# STM32_CONNECTORS.net
KiCad netlist of a schematic drawn in Altium Designer
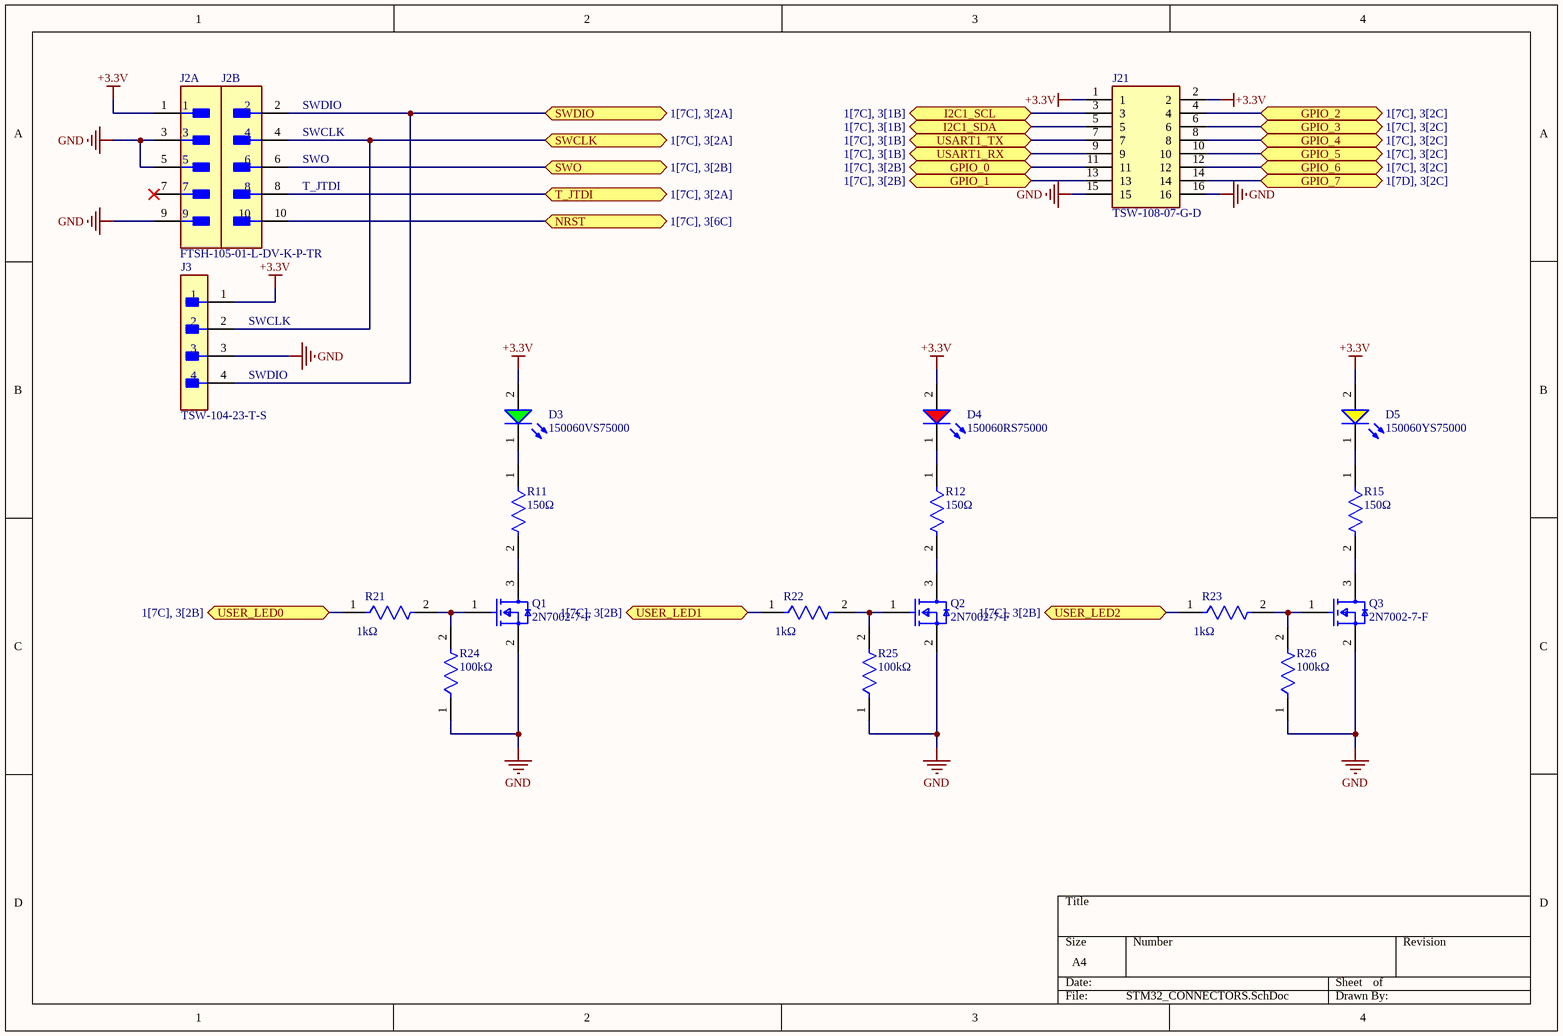
[diagram p0: STM32_CONNECTORS.SchDoc]

(export (version "E")
  (design (tool "Eeschema 10.0.6"))
  (components
    (comp (ref "D3")
      (value "150060VS75000")
      (footprint "WL-SMCW_0603_150060xx75000")
      (libsource (lib "Altium Content Vault") (part "LED_Green_2A-1K"))
    )
    (comp (ref "D4")
      (value "150060RS75000")
      (footprint "WL-SMCW_0603_150060xx75000")
      (libsource (lib "Altium Content Vault") (part "LED_Red_2A-1K"))
    )
    (comp (ref "D5")
      (value "150060YS75000")
      (footprint "WL-SMCW_0603_150060xx75000")
      (libsource (lib "Altium Content Vault") (part "LED_Yellow_2A-1K"))
    )
    (comp (ref "J2")
      (value "FTSH-105-01-L-DV-K-P-TR")
      (footprint "FP-FTSH-105-01-L-DV-K-P-T-MFG")
      (description "CONN HEADER SMD 10POS 1.27MM")
      (libsource (lib "") (part "544f42128f4185dcb88ce1ce9bf1982_1"))
    )
    (comp (ref "J3")
      (value "TSW-104-23-T-S")
      (footprint "FP-TSW-104-23-T-S-MFG")
      (description "CONN HEADER VERT 4POS 2.54MM")
      (libsource (lib "Altium Content Vault") (part "f33e0d423099bbb9e64512431cdbdf7"))
    )
    (comp (ref "J21")
      (value "TSW-108-07-G-D")
      (footprint "SamacSys:HDRV16W64P254_2X8_2032X508X838P")
      (description "Connector")
      (fields (field (name "MOUSER PART NUMBER") "200-TSW10807GD"))
      (libsource (lib "*") (part "TSW-108-07-G-D"))
    )
    (comp (ref "Q1")
      (value "2N7002-7-F")
      (footprint "FP-SOT23-IPC_A")
      (description "MOSFET N-CH 60V 115MA SOT23-3")
      (fields (field (name "VOLTAGE") "60V"))
      (libsource (lib "Altium Content Vault") (part "3b9c635fedb024a5347a57b145af9cc"))
    )
    (comp (ref "Q2")
      (value "2N7002-7-F")
      (footprint "FP-SOT23-IPC_A")
      (description "MOSFET N-CH 60V 115MA SOT23-3")
      (fields (field (name "VOLTAGE") "60V"))
      (libsource (lib "Altium Content Vault") (part "3b9c635fedb024a5347a57b145af9cc"))
    )
    (comp (ref "Q3")
      (value "2N7002-7-F")
      (footprint "FP-SOT23-IPC_A")
      (description "MOSFET N-CH 60V 115MA SOT23-3")
      (fields (field (name "VOLTAGE") "60V"))
      (libsource (lib "Altium Content Vault") (part "3b9c635fedb024a5347a57b145af9cc"))
    )
    (comp (ref "R11")
      (value "CRCW0603150RFKEA")
      (footprint "FP-CRCW0603-e3-IPC_B")
      (description "RES Thick Film, 150Ω, 1%, 0.1W, 100ppm/°C, 0603")
      (fields (field (name "TOLERANCE") "1%") (field (name "RESISTANCE") "150Ω"))
      (libsource (lib "Altium Content Vault") (part "1029c3af85768c4190bb7ad29bc67b5"))
    )
    (comp (ref "R12")
      (value "CRCW0603150RFKEA")
      (footprint "FP-CRCW0603-e3-IPC_B")
      (description "RES Thick Film, 150Ω, 1%, 0.1W, 100ppm/°C, 0603")
      (fields (field (name "TOLERANCE") "1%") (field (name "RESISTANCE") "150Ω"))
      (libsource (lib "Altium Content Vault") (part "1029c3af85768c4190bb7ad29bc67b5"))
    )
    (comp (ref "R15")
      (value "CRCW0603150RFKEA")
      (footprint "FP-CRCW0603-e3-IPC_B")
      (description "RES Thick Film, 150Ω, 1%, 0.1W, 100ppm/°C, 0603")
      (fields (field (name "TOLERANCE") "1%") (field (name "RESISTANCE") "150Ω"))
      (libsource (lib "Altium Content Vault") (part "1029c3af85768c4190bb7ad29bc67b5"))
    )
    (comp (ref "R21")
      (value "AC0603FR-071KL")
      (footprint "FP-AC0603-IPC_B")
      (description "RES 1kΩ 1.00% 0.1W 0603")
      (fields (field (name "TOLERANCE") "1%") (field (name "RESISTANCE") "1kΩ"))
      (libsource (lib "Altium Content Vault") (part "1029c3af85768c4190bb7ad29bc67b5"))
    )
    (comp (ref "R22")
      (value "AC0603FR-071KL")
      (footprint "FP-AC0603-IPC_B")
      (description "RES 1kΩ 1.00% 0.1W 0603")
      (fields (field (name "TOLERANCE") "1%") (field (name "RESISTANCE") "1kΩ"))
      (libsource (lib "Altium Content Vault") (part "1029c3af85768c4190bb7ad29bc67b5"))
    )
    (comp (ref "R23")
      (value "AC0603FR-071KL")
      (footprint "FP-AC0603-IPC_B")
      (description "RES 1kΩ 1.00% 0.1W 0603")
      (fields (field (name "TOLERANCE") "1%") (field (name "RESISTANCE") "1kΩ"))
      (libsource (lib "Altium Content Vault") (part "1029c3af85768c4190bb7ad29bc67b5"))
    )
    (comp (ref "R24")
      (value "CRCW0603100KFKEC")
      (footprint "FP-CRCW0603-e3-IPC_B")
      (description "RES Thick Film, 100kΩ, 1%, 0.1W, 100ppm/°C, 0603")
      (fields (field (name "RESISTANCE") "100kΩ") (field (name "TOLERANCE") "1%"))
      (libsource (lib "Altium Content Vault") (part "1029c3af85768c4190bb7ad29bc67b5"))
    )
    (comp (ref "R25")
      (value "CRCW0603100KFKEC")
      (footprint "FP-CRCW0603-e3-IPC_B")
      (description "RES Thick Film, 100kΩ, 1%, 0.1W, 100ppm/°C, 0603")
      (fields (field (name "RESISTANCE") "100kΩ") (field (name "TOLERANCE") "1%"))
      (libsource (lib "Altium Content Vault") (part "1029c3af85768c4190bb7ad29bc67b5"))
    )
    (comp (ref "R26")
      (value "CRCW0603100KFKEC")
      (footprint "FP-CRCW0603-e3-IPC_B")
      (description "RES Thick Film, 100kΩ, 1%, 0.1W, 100ppm/°C, 0603")
      (fields (field (name "RESISTANCE") "100kΩ") (field (name "TOLERANCE") "1%"))
      (libsource (lib "Altium Content Vault") (part "1029c3af85768c4190bb7ad29bc67b5"))
    )
  )
  (nets
    (net (code "1") (name "+3.3V") (class "Default")
      (node (ref "D3") (pin "2") (pinfunction "A_2") (pintype "passive"))
      (node (ref "D4") (pin "2") (pinfunction "A_2") (pintype "passive"))
      (node (ref "D5") (pin "2") (pinfunction "A_2") (pintype "passive"))
      (node (ref "J2") (pin "1") (pinfunction "1_1") (pintype "passive"))
      (node (ref "J21") (pin "1") (pinfunction "1_1") (pintype "passive"))
      (node (ref "J21") (pin "2") (pinfunction "2_2") (pintype "passive"))
      (node (ref "J3") (pin "1") (pinfunction "1_1") (pintype "passive"))
    )
    (net (code "2") (name "/GPIO_0") (class "Default")
      (node (ref "J21") (pin "11") (pinfunction "11_11") (pintype "passive"))
    )
    (net (code "3") (name "/GPIO_1") (class "Default")
      (node (ref "J21") (pin "13") (pinfunction "13_13") (pintype "passive"))
    )
    (net (code "4") (name "/GPIO_2") (class "Default")
      (node (ref "J21") (pin "4") (pinfunction "4_4") (pintype "passive"))
    )
    (net (code "5") (name "/GPIO_3") (class "Default")
      (node (ref "J21") (pin "6") (pinfunction "6_6") (pintype "passive"))
    )
    (net (code "6") (name "/GPIO_4") (class "Default")
      (node (ref "J21") (pin "8") (pinfunction "8_8") (pintype "passive"))
    )
    (net (code "7") (name "/GPIO_5") (class "Default")
      (node (ref "J21") (pin "10") (pinfunction "10_10") (pintype "passive"))
    )
    (net (code "8") (name "/GPIO_6") (class "Default")
      (node (ref "J21") (pin "12") (pinfunction "12_12") (pintype "passive"))
    )
    (net (code "9") (name "/GPIO_7") (class "Default")
      (node (ref "J21") (pin "14") (pinfunction "14_14") (pintype "passive"))
    )
    (net (code "10") (name "/I2C1_SCL") (class "Default")
      (node (ref "J21") (pin "3") (pinfunction "3_3") (pintype "passive"))
    )
    (net (code "11") (name "/I2C1_SDA") (class "Default")
      (node (ref "J21") (pin "5") (pinfunction "5_5") (pintype "passive"))
    )
    (net (code "12") (name "/NRST") (class "Default")
      (node (ref "J2") (pin "10") (pinfunction "10_10") (pintype "passive"))
    )
    (net (code "13") (name "/SWCLK") (class "Default")
      (node (ref "J2") (pin "4") (pinfunction "4_4") (pintype "passive"))
      (node (ref "J3") (pin "2") (pinfunction "2_2") (pintype "passive"))
    )
    (net (code "14") (name "/SWDIO") (class "Default")
      (node (ref "J2") (pin "2") (pinfunction "2_2") (pintype "passive"))
      (node (ref "J3") (pin "4") (pinfunction "4_4") (pintype "passive"))
    )
    (net (code "15") (name "/SWO") (class "Default")
      (node (ref "J2") (pin "6") (pinfunction "6_6") (pintype "passive"))
    )
    (net (code "16") (name "/T_JTDI") (class "Default")
      (node (ref "J2") (pin "8") (pinfunction "8_8") (pintype "passive"))
    )
    (net (code "17") (name "/USART1_RX") (class "Default")
      (node (ref "J21") (pin "9") (pinfunction "9_9") (pintype "passive"))
    )
    (net (code "18") (name "/USART1_TX") (class "Default")
      (node (ref "J21") (pin "7") (pinfunction "7_7") (pintype "passive"))
    )
    (net (code "19") (name "/USER_LED0") (class "Default")
      (node (ref "R21") (pin "1") (pinfunction "1_1") (pintype "passive"))
    )
    (net (code "20") (name "/USER_LED1") (class "Default")
      (node (ref "R22") (pin "1") (pinfunction "1_1") (pintype "passive"))
    )
    (net (code "21") (name "/USER_LED2") (class "Default")
      (node (ref "R23") (pin "1") (pinfunction "1_1") (pintype "passive"))
    )
    (net (code "22") (name "GND") (class "Default")
      (node (ref "J2") (pin "3") (pinfunction "3_3") (pintype "passive"))
      (node (ref "J2") (pin "5") (pinfunction "5_5") (pintype "passive"))
      (node (ref "J2") (pin "9") (pinfunction "9_9") (pintype "passive"))
      (node (ref "J21") (pin "15") (pinfunction "15_15") (pintype "passive"))
      (node (ref "J21") (pin "16") (pinfunction "16_16") (pintype "passive"))
      (node (ref "J3") (pin "3") (pinfunction "3_3") (pintype "passive"))
      (node (ref "Q1") (pin "2") (pinfunction "S_2") (pintype "passive"))
      (node (ref "Q2") (pin "2") (pinfunction "S_2") (pintype "passive"))
      (node (ref "Q3") (pin "2") (pinfunction "S_2") (pintype "passive"))
      (node (ref "R24") (pin "1") (pinfunction "1_1") (pintype "passive"))
      (node (ref "R25") (pin "1") (pinfunction "1_1") (pintype "passive"))
      (node (ref "R26") (pin "1") (pinfunction "1_1") (pintype "passive"))
    )
    (net (code "23") (name "Net-(D3-K)") (class "Default")
      (node (ref "D3") (pin "1") (pinfunction "K_1") (pintype "passive"))
      (node (ref "R11") (pin "1") (pinfunction "1_1") (pintype "passive"))
    )
    (net (code "24") (name "Net-(D4-K)") (class "Default")
      (node (ref "D4") (pin "1") (pinfunction "K_1") (pintype "passive"))
      (node (ref "R12") (pin "1") (pinfunction "1_1") (pintype "passive"))
    )
    (net (code "25") (name "Net-(D5-K)") (class "Default")
      (node (ref "D5") (pin "1") (pinfunction "K_1") (pintype "passive"))
      (node (ref "R15") (pin "1") (pinfunction "1_1") (pintype "passive"))
    )
    (net (code "26") (name "Net-(Q1-D)") (class "Default")
      (node (ref "Q1") (pin "3") (pinfunction "D_3") (pintype "passive"))
      (node (ref "R11") (pin "2") (pinfunction "2_2") (pintype "passive"))
    )
    (net (code "27") (name "Net-(Q1-G)") (class "Default")
      (node (ref "Q1") (pin "1") (pinfunction "G_1") (pintype "passive"))
      (node (ref "R21") (pin "2") (pinfunction "2_2") (pintype "passive"))
      (node (ref "R24") (pin "2") (pinfunction "2_2") (pintype "passive"))
    )
    (net (code "28") (name "Net-(Q2-D)") (class "Default")
      (node (ref "Q2") (pin "3") (pinfunction "D_3") (pintype "passive"))
      (node (ref "R12") (pin "2") (pinfunction "2_2") (pintype "passive"))
    )
    (net (code "29") (name "Net-(Q2-G)") (class "Default")
      (node (ref "Q2") (pin "1") (pinfunction "G_1") (pintype "passive"))
      (node (ref "R22") (pin "2") (pinfunction "2_2") (pintype "passive"))
      (node (ref "R25") (pin "2") (pinfunction "2_2") (pintype "passive"))
    )
    (net (code "30") (name "Net-(Q3-D)") (class "Default")
      (node (ref "Q3") (pin "3") (pinfunction "D_3") (pintype "passive"))
      (node (ref "R15") (pin "2") (pinfunction "2_2") (pintype "passive"))
    )
    (net (code "31") (name "Net-(Q3-G)") (class "Default")
      (node (ref "Q3") (pin "1") (pinfunction "G_1") (pintype "passive"))
      (node (ref "R23") (pin "2") (pinfunction "2_2") (pintype "passive"))
      (node (ref "R26") (pin "2") (pinfunction "2_2") (pintype "passive"))
    )
    (net (code "32") (name "unconnected-(J2-Pad7)") (class "Default")
      (node (ref "J2") (pin "7") (pinfunction "7_7") (pintype "passive+no_connect"))
    )
  )
)
